# AIOT_02.net
KiCad netlist of a schematic drawn in EAGLE
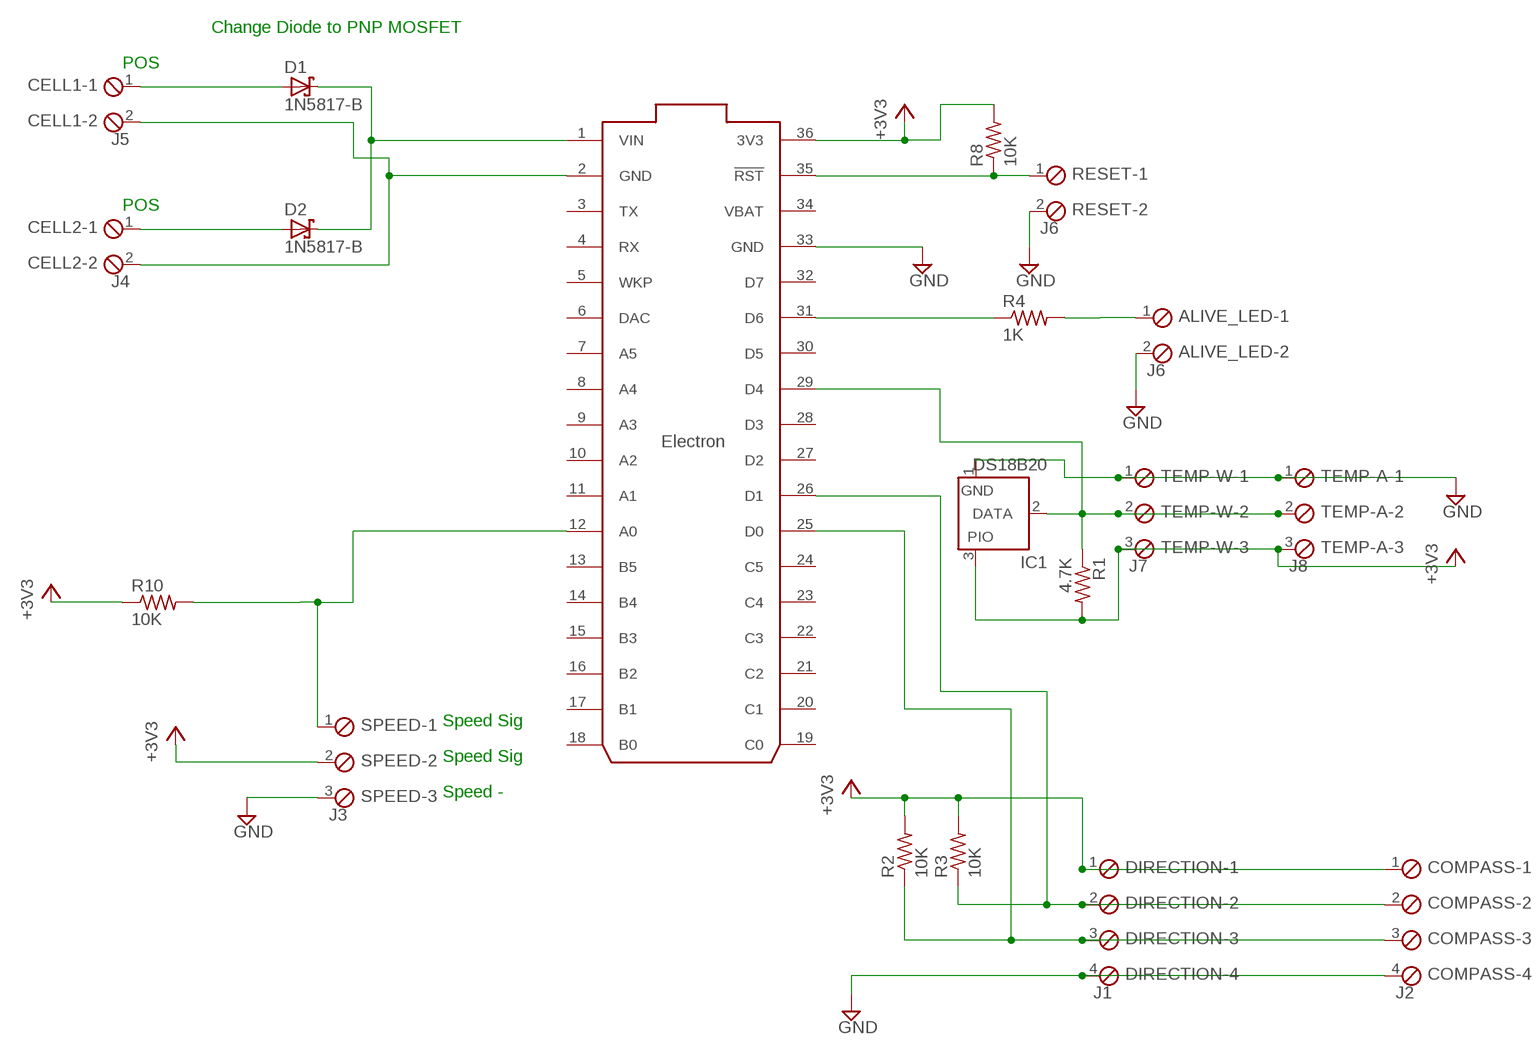
[diagram p0: schematic, sheet 1]

(export (version "E")
  (design (tool "Eeschema 10.0.6"))
  (components
    (comp (ref "ALIVE_LED")
      (value "J6")
      (footprint "eagle-import:2POL254")
      (libsource (lib "eagle-import") (part "MPT2"))
    )
    (comp (ref "CELL1")
      (value "J5")
      (footprint "eagle-import:2POL254")
      (libsource (lib "eagle-import") (part "MPT2"))
    )
    (comp (ref "CELL2")
      (value "J4")
      (footprint "eagle-import:2POL254")
      (libsource (lib "eagle-import") (part "MPT2"))
    )
    (comp (ref "COMPASS")
      (value "J2")
      (footprint "eagle-import:4POL254")
      (libsource (lib "eagle-import") (part "MPT4"))
    )
    (comp (ref "D1")
      (value "1N5817-B")
      (footprint "eagle-import:DO41-7.6")
      (libsource (lib "eagle-import") (part "1N5817-B"))
    )
    (comp (ref "D2")
      (value "1N5817-B")
      (footprint "eagle-import:DO41-7.6")
      (libsource (lib "eagle-import") (part "1N5817-B"))
    )
    (comp (ref "DIRECTION")
      (value "J1")
      (footprint "eagle-import:4POL254")
      (libsource (lib "eagle-import") (part "MPT4"))
    )
    (comp (ref "IC1")
      (value "DS18B20")
      (footprint "eagle-import:TO92-")
      (fields (field (name "MF") "DALLAS SEMICONDUCTOR") (field (name "MPN") "DS2405"))
      (libsource (lib "eagle-import") (part "DS2405"))
    )
    (comp (ref "R1")
      (value "4.7K")
      (footprint "eagle-import:R1210")
      (libsource (lib "eagle-import") (part "R-US_R1210"))
    )
    (comp (ref "R2")
      (value "10K")
      (footprint "eagle-import:R1210")
      (libsource (lib "eagle-import") (part "R-US_R1210"))
    )
    (comp (ref "R3")
      (value "10K")
      (footprint "eagle-import:R1210")
      (libsource (lib "eagle-import") (part "R-US_R1210"))
    )
    (comp (ref "R4")
      (value "1K")
      (footprint "eagle-import:R1210")
      (libsource (lib "eagle-import") (part "R-US_R1210"))
    )
    (comp (ref "R8")
      (value "10K")
      (footprint "eagle-import:R1210")
      (libsource (lib "eagle-import") (part "R-US_R1210"))
    )
    (comp (ref "R10")
      (value "10K")
      (footprint "eagle-import:R1210")
      (libsource (lib "eagle-import") (part "R-US_R1210"))
    )
    (comp (ref "RESET")
      (value "J6")
      (footprint "eagle-import:2POL254")
      (libsource (lib "eagle-import") (part "MPT2"))
    )
    (comp (ref "SPEED")
      (value "J3")
      (footprint "eagle-import:3POL254")
      (libsource (lib "eagle-import") (part "MPT3"))
    )
    (comp (ref "TEMP-A")
      (value "J8")
      (footprint "eagle-import:3POL254")
      (libsource (lib "eagle-import") (part "MPT3"))
    )
    (comp (ref "TEMP-W")
      (value "J7")
      (footprint "eagle-import:3POL254")
      (libsource (lib "eagle-import") (part "MPT3"))
    )
    (comp (ref "U$1")
      (value "ELECTRON_WITH_HEADERS")
      (footprint "eagle-import:ELECTRON")
      (libsource (lib "eagle-import") (part "ELECTRON_WITH_HEADERS"))
    )
  )
  (nets
    (net (code "1") (name "+3V3") (class "Default")
      (node (ref "COMPASS") (pin "1") (pinfunction "1_1") (pintype "passive"))
      (node (ref "DIRECTION") (pin "1") (pinfunction "1_1") (pintype "passive"))
      (node (ref "IC1") (pin "3") (pinfunction "PIO_3") (pintype "passive"))
      (node (ref "R1") (pin "2") (pinfunction "2_2") (pintype "passive"))
      (node (ref "R10") (pin "1") (pinfunction "1_1") (pintype "passive"))
      (node (ref "R2") (pin "2") (pinfunction "2_2") (pintype "passive"))
      (node (ref "R3") (pin "2") (pinfunction "2_2") (pintype "passive"))
      (node (ref "R8") (pin "2") (pinfunction "2_2") (pintype "passive"))
      (node (ref "SPEED") (pin "2") (pinfunction "1_2") (pintype "passive"))
      (node (ref "TEMP-A") (pin "3") (pinfunction "1_3") (pintype "passive"))
      (node (ref "TEMP-W") (pin "3") (pinfunction "1_3") (pintype "passive"))
      (node (ref "U$1") (pin "36") (pinfunction "3V3_36") (pintype "power_in"))
    )
    (net (code "2") (name "/VBAT") (class "Default")
      (node (ref "U$1") (pin "34") (pinfunction "VBAT_34") (pintype "power_in"))
    )
    (net (code "3") (name "GND") (class "Default")
      (node (ref "ALIVE_LED") (pin "2") (pinfunction "1_2") (pintype "passive"))
      (node (ref "CELL1") (pin "2") (pinfunction "1_2") (pintype "passive"))
      (node (ref "CELL2") (pin "2") (pinfunction "1_2") (pintype "passive"))
      (node (ref "COMPASS") (pin "4") (pinfunction "1_4") (pintype "passive"))
      (node (ref "DIRECTION") (pin "4") (pinfunction "1_4") (pintype "passive"))
      (node (ref "IC1") (pin "1") (pinfunction "GND_1") (pintype "passive"))
      (node (ref "RESET") (pin "2") (pinfunction "1_2") (pintype "passive"))
      (node (ref "SPEED") (pin "3") (pinfunction "1_3") (pintype "passive"))
      (node (ref "TEMP-A") (pin "1") (pinfunction "1_1") (pintype "passive"))
      (node (ref "TEMP-W") (pin "1") (pinfunction "1_1") (pintype "passive"))
      (node (ref "U$1") (pin "2") (pinfunction "GND_2") (pintype "power_in"))
      (node (ref "U$1") (pin "33") (pinfunction "GND_33") (pintype "power_in"))
    )
    (net (code "4") (name "Net-(ALIVE_LED-Pad1)") (class "Default")
      (node (ref "ALIVE_LED") (pin "1") (pinfunction "1_1") (pintype "passive"))
      (node (ref "R4") (pin "2") (pinfunction "2_2") (pintype "passive"))
    )
    (net (code "5") (name "Net-(CELL1-Pad1)") (class "Default")
      (node (ref "CELL1") (pin "1") (pinfunction "1_1") (pintype "passive"))
      (node (ref "D1") (pin "A") (pinfunction "A_A") (pintype "passive"))
    )
    (net (code "6") (name "Net-(CELL2-Pad1)") (class "Default")
      (node (ref "CELL2") (pin "1") (pinfunction "1_1") (pintype "passive"))
      (node (ref "D2") (pin "A") (pinfunction "A_A") (pintype "passive"))
    )
    (net (code "7") (name "Net-(COMPASSB-1)") (class "Default")
      (node (ref "COMPASS") (pin "2") (pinfunction "1_2") (pintype "passive"))
      (node (ref "DIRECTION") (pin "2") (pinfunction "1_2") (pintype "passive"))
      (node (ref "R3") (pin "1") (pinfunction "1_1") (pintype "passive"))
      (node (ref "U$1") (pin "26") (pinfunction "D1_26") (pintype "bidirectional"))
    )
    (net (code "8") (name "Net-(COMPASSC-1)") (class "Default")
      (node (ref "COMPASS") (pin "3") (pinfunction "1_3") (pintype "passive"))
      (node (ref "DIRECTION") (pin "3") (pinfunction "1_3") (pintype "passive"))
      (node (ref "R2") (pin "1") (pinfunction "1_1") (pintype "passive"))
      (node (ref "U$1") (pin "25") (pinfunction "D0_25") (pintype "bidirectional"))
    )
    (net (code "9") (name "Net-(IC1-DATA)") (class "Default")
      (node (ref "IC1") (pin "2") (pinfunction "DATA_2") (pintype "input"))
      (node (ref "R1") (pin "1") (pinfunction "1_1") (pintype "passive"))
      (node (ref "TEMP-A") (pin "2") (pinfunction "1_2") (pintype "passive"))
      (node (ref "TEMP-W") (pin "2") (pinfunction "1_2") (pintype "passive"))
      (node (ref "U$1") (pin "29") (pinfunction "D4_29") (pintype "bidirectional"))
    )
    (net (code "10") (name "Net-(U$1-A0)") (class "Default")
      (node (ref "R10") (pin "2") (pinfunction "2_2") (pintype "passive"))
      (node (ref "SPEED") (pin "1") (pinfunction "1_1") (pintype "passive"))
      (node (ref "U$1") (pin "12") (pinfunction "A0_12") (pintype "bidirectional"))
    )
    (net (code "11") (name "Net-(U$1-D6)") (class "Default")
      (node (ref "R4") (pin "1") (pinfunction "1_1") (pintype "passive"))
      (node (ref "U$1") (pin "31") (pinfunction "D6_31") (pintype "bidirectional"))
    )
    (net (code "12") (name "Net-(U$1-VIN)") (class "Default")
      (node (ref "D1") (pin "C") (pinfunction "C_C") (pintype "passive"))
      (node (ref "D2") (pin "C") (pinfunction "C_C") (pintype "passive"))
      (node (ref "U$1") (pin "1") (pinfunction "VIN_1") (pintype "power_in"))
    )
    (net (code "13") (name "Net-(U$1-~{RST})") (class "Default")
      (node (ref "R8") (pin "1") (pinfunction "1_1") (pintype "passive"))
      (node (ref "RESET") (pin "1") (pinfunction "1_1") (pintype "passive"))
      (node (ref "U$1") (pin "35") (pinfunction "~{RST}_35") (pintype "bidirectional"))
    )
    (net (code "14") (name "unconnected-(U$1-A1-Pad11)") (class "Default")
      (node (ref "U$1") (pin "11") (pinfunction "A1_11") (pintype "bidirectional"))
    )
    (net (code "15") (name "unconnected-(U$1-A2-Pad10)") (class "Default")
      (node (ref "U$1") (pin "10") (pinfunction "A2_10") (pintype "bidirectional"))
    )
    (net (code "16") (name "unconnected-(U$1-A3-Pad9)") (class "Default")
      (node (ref "U$1") (pin "9") (pinfunction "A3_9") (pintype "bidirectional"))
    )
    (net (code "17") (name "unconnected-(U$1-A4-Pad8)") (class "Default")
      (node (ref "U$1") (pin "8") (pinfunction "A4_8") (pintype "bidirectional"))
    )
    (net (code "18") (name "unconnected-(U$1-A5-Pad7)") (class "Default")
      (node (ref "U$1") (pin "7") (pinfunction "A5_7") (pintype "bidirectional"))
    )
    (net (code "19") (name "unconnected-(U$1-B0-Pad18)") (class "Default")
      (node (ref "U$1") (pin "18") (pinfunction "B0_18") (pintype "bidirectional"))
    )
    (net (code "20") (name "unconnected-(U$1-B1-Pad17)") (class "Default")
      (node (ref "U$1") (pin "17") (pinfunction "B1_17") (pintype "bidirectional"))
    )
    (net (code "21") (name "unconnected-(U$1-B2-Pad16)") (class "Default")
      (node (ref "U$1") (pin "16") (pinfunction "B2_16") (pintype "bidirectional"))
    )
    (net (code "22") (name "unconnected-(U$1-B3-Pad15)") (class "Default")
      (node (ref "U$1") (pin "15") (pinfunction "B3_15") (pintype "bidirectional"))
    )
    (net (code "23") (name "unconnected-(U$1-B4-Pad14)") (class "Default")
      (node (ref "U$1") (pin "14") (pinfunction "B4_14") (pintype "bidirectional"))
    )
    (net (code "24") (name "unconnected-(U$1-B5-Pad13)") (class "Default")
      (node (ref "U$1") (pin "13") (pinfunction "B5_13") (pintype "bidirectional"))
    )
    (net (code "25") (name "unconnected-(U$1-C0-Pad19)") (class "Default")
      (node (ref "U$1") (pin "19") (pinfunction "C0_19") (pintype "bidirectional"))
    )
    (net (code "26") (name "unconnected-(U$1-C1-Pad20)") (class "Default")
      (node (ref "U$1") (pin "20") (pinfunction "C1_20") (pintype "bidirectional"))
    )
    (net (code "27") (name "unconnected-(U$1-C2-Pad21)") (class "Default")
      (node (ref "U$1") (pin "21") (pinfunction "C2_21") (pintype "bidirectional"))
    )
    (net (code "28") (name "unconnected-(U$1-C3-Pad22)") (class "Default")
      (node (ref "U$1") (pin "22") (pinfunction "C3_22") (pintype "bidirectional"))
    )
    (net (code "29") (name "unconnected-(U$1-C4-Pad23)") (class "Default")
      (node (ref "U$1") (pin "23") (pinfunction "C4_23") (pintype "bidirectional"))
    )
    (net (code "30") (name "unconnected-(U$1-C5-Pad24)") (class "Default")
      (node (ref "U$1") (pin "24") (pinfunction "C5_24") (pintype "bidirectional"))
    )
    (net (code "31") (name "unconnected-(U$1-D2-Pad27)") (class "Default")
      (node (ref "U$1") (pin "27") (pinfunction "D2_27") (pintype "bidirectional"))
    )
    (net (code "32") (name "unconnected-(U$1-D3-Pad28)") (class "Default")
      (node (ref "U$1") (pin "28") (pinfunction "D3_28") (pintype "bidirectional"))
    )
    (net (code "33") (name "unconnected-(U$1-D5-Pad30)") (class "Default")
      (node (ref "U$1") (pin "30") (pinfunction "D5_30") (pintype "bidirectional"))
    )
    (net (code "34") (name "unconnected-(U$1-D7-Pad32)") (class "Default")
      (node (ref "U$1") (pin "32") (pinfunction "D7_32") (pintype "bidirectional"))
    )
    (net (code "35") (name "unconnected-(U$1-DAC-Pad6)") (class "Default")
      (node (ref "U$1") (pin "6") (pinfunction "DAC_6") (pintype "bidirectional"))
    )
    (net (code "36") (name "unconnected-(U$1-RX-Pad4)") (class "Default")
      (node (ref "U$1") (pin "4") (pinfunction "RX_4") (pintype "bidirectional"))
    )
    (net (code "37") (name "unconnected-(U$1-TX-Pad3)") (class "Default")
      (node (ref "U$1") (pin "3") (pinfunction "TX_3") (pintype "bidirectional"))
    )
    (net (code "38") (name "unconnected-(U$1-WKP-Pad5)") (class "Default")
      (node (ref "U$1") (pin "5") (pinfunction "WKP_5") (pintype "bidirectional"))
    )
  )
)
